# LeftInterface.net
KiCad netlist of a schematic drawn in Altium Designer
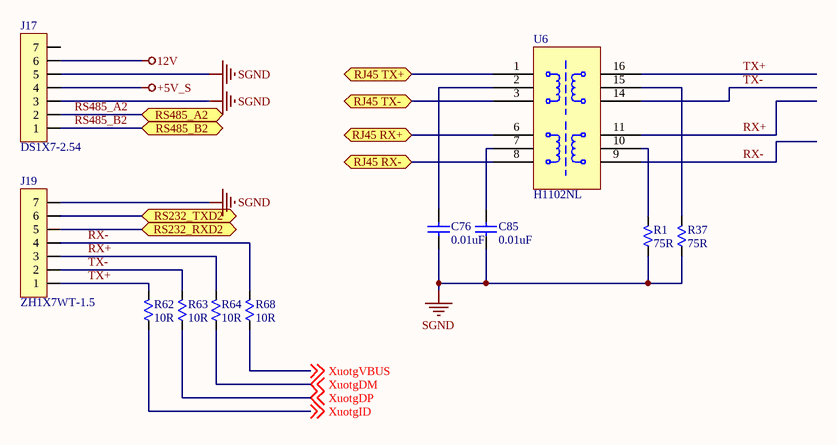
[diagram p0: LeftInterface.SchDoc]

(export (version "E")
  (design (tool "Eeschema 10.0.6"))
  (components
    (comp (ref "C76")
      (value "0.01uF")
      (footprint "C0805")
      (description "Capacitor")
      (fields (field (name "PUBLISHER") "Altium Limited"))
      (libsource (lib "Miscellaneous Devices") (part "Cap"))
    )
    (comp (ref "C85")
      (value "0.01uF")
      (footprint "C0805")
      (description "Capacitor")
      (fields (field (name "PUBLISHER") "Altium Limited"))
      (libsource (lib "Miscellaneous Devices") (part "Cap"))
    )
    (comp (ref "J17")
      (value "DS1X7-2.54")
      (footprint "DS1X7H-2.54")
      (libsource (lib "Connector Class") (part "HEADER1X7"))
    )
    (comp (ref "J19")
      (value "ZH1X7WT-1.5")
      (footprint "ZH1X7WT-1.5")
      (libsource (lib "Connector Class") (part "HEADER1X7"))
    )
    (comp (ref "R1")
      (value "75R")
      (footprint "R0805")
      (description "Resistor")
      (fields (field (name "PUBLISHER") "Altium Limited"))
      (libsource (lib "UP-Robot") (part "Res"))
    )
    (comp (ref "R37")
      (value "75R")
      (footprint "R0805")
      (description "Resistor")
      (fields (field (name "PUBLISHER") "Altium Limited"))
      (libsource (lib "UP-Robot") (part "Res"))
    )
    (comp (ref "R62")
      (value "10R")
      (footprint "R0805")
      (description "Resistor")
      (fields (field (name "PUBLISHER") "Altium Limited"))
      (libsource (lib "UP-Robot") (part "Res"))
    )
    (comp (ref "R63")
      (value "10R")
      (footprint "R0805")
      (description "Resistor")
      (fields (field (name "PUBLISHER") "Altium Limited"))
      (libsource (lib "UP-Robot") (part "Res"))
    )
    (comp (ref "R64")
      (value "10R")
      (footprint "R0805")
      (description "Resistor")
      (fields (field (name "PUBLISHER") "Altium Limited"))
      (libsource (lib "UP-Robot") (part "Res"))
    )
    (comp (ref "R68")
      (value "10R")
      (footprint "R0805")
      (description "Resistor")
      (fields (field (name "PUBLISHER") "Altium Limited"))
      (libsource (lib "UP-Robot") (part "Res"))
    )
    (comp (ref "U6")
      (value "H1102NL")
      (footprint "SOP16")
      (libsource (lib "Productor Class") (part "H1102NL"))
    )
  )
  (nets
    (net (code "1") (name "+5V_S") (class "Default")
      (node (ref "J17") (pin "4") (pinfunction "4_4") (pintype "passive"))
    )
    (net (code "2") (name "/RJ45 RX+") (class "Default") (node (ref "U6") (pin "6") (pintype "passive")))
    (net (code "3") (name "/RJ45 RX-") (class "Default") (node (ref "U6") (pin "8") (pintype "passive")))
    (net (code "4") (name "/RJ45 TX+") (class "Default") (node (ref "U6") (pin "1") (pintype "passive")))
    (net (code "5") (name "/RJ45 TX-") (class "Default") (node (ref "U6") (pin "3") (pintype "passive")))
    (net (code "6") (name "/RS232_RXD2") (class "Default")
      (node (ref "J19") (pin "5") (pinfunction "5_5") (pintype "passive"))
    )
    (net (code "7") (name "/RS232_TXD2") (class "Default")
      (node (ref "J19") (pin "6") (pinfunction "6_6") (pintype "passive"))
    )
    (net (code "8") (name "/RS485_A2") (class "Default")
      (node (ref "J17") (pin "2") (pinfunction "2_2") (pintype "passive"))
    )
    (net (code "9") (name "/RS485_B2") (class "Default")
      (node (ref "J17") (pin "1") (pinfunction "1_1") (pintype "passive"))
    )
    (net (code "10") (name "/RX+") (class "Default")
      (node (ref "J19") (pin "3") (pinfunction "3_3") (pintype "passive"))
      (node (ref "R64") (pin "1") (pinfunction "1_1") (pintype "passive"))
      (node (ref "U6") (pin "11") (pintype "passive"))
    )
    (net (code "11") (name "/RX-") (class "Default")
      (node (ref "J19") (pin "4") (pinfunction "4_4") (pintype "passive"))
      (node (ref "R68") (pin "1") (pinfunction "1_1") (pintype "passive"))
      (node (ref "U6") (pin "9") (pintype "passive"))
    )
    (net (code "12") (name "/TX+") (class "Default")
      (node (ref "J19") (pin "1") (pinfunction "1_1") (pintype "passive"))
      (node (ref "R62") (pin "1") (pinfunction "1_1") (pintype "passive"))
      (node (ref "U6") (pin "16") (pintype "passive"))
    )
    (net (code "13") (name "/TX-") (class "Default")
      (node (ref "J19") (pin "2") (pinfunction "2_2") (pintype "passive"))
      (node (ref "R63") (pin "1") (pinfunction "1_1") (pintype "passive"))
      (node (ref "U6") (pin "14") (pintype "passive"))
    )
    (net (code "14") (name "12V") (class "Default")
      (node (ref "J17") (pin "6") (pinfunction "6_6") (pintype "passive"))
    )
    (net (code "15") (name "Net-(C76-Pad1)") (class "Default")
      (node (ref "C76") (pin "1") (pinfunction "1_1") (pintype "passive"))
      (node (ref "U6") (pin "2") (pintype "passive"))
    )
    (net (code "16") (name "Net-(C85-Pad1)") (class "Default")
      (node (ref "C85") (pin "1") (pinfunction "1_1") (pintype "passive"))
      (node (ref "U6") (pin "7") (pintype "passive"))
    )
    (net (code "17") (name "Net-(R1-Pad1)") (class "Default")
      (node (ref "R1") (pin "1") (pinfunction "1_1") (pintype "passive"))
      (node (ref "U6") (pin "10") (pintype "passive"))
    )
    (net (code "18") (name "Net-(R37-Pad1)") (class "Default")
      (node (ref "R37") (pin "1") (pinfunction "1_1") (pintype "passive"))
      (node (ref "U6") (pin "15") (pintype "passive"))
    )
    (net (code "19") (name "SGND") (class "Default")
      (node (ref "C76") (pin "2") (pinfunction "2_2") (pintype "passive"))
      (node (ref "C85") (pin "2") (pinfunction "2_2") (pintype "passive"))
      (node (ref "J17") (pin "3") (pinfunction "3_3") (pintype "passive"))
      (node (ref "J17") (pin "5") (pinfunction "5_5") (pintype "passive"))
      (node (ref "J19") (pin "7") (pinfunction "7_7") (pintype "passive"))
      (node (ref "R1") (pin "2") (pinfunction "2_2") (pintype "passive"))
      (node (ref "R37") (pin "2") (pinfunction "2_2") (pintype "passive"))
    )
    (net (code "20") (name "XuotgDM") (class "Default")
      (node (ref "R64") (pin "2") (pinfunction "2_2") (pintype "passive"))
    )
    (net (code "21") (name "XuotgDP") (class "Default")
      (node (ref "R63") (pin "2") (pinfunction "2_2") (pintype "passive"))
    )
    (net (code "22") (name "XuotgID") (class "Default")
      (node (ref "R62") (pin "2") (pinfunction "2_2") (pintype "passive"))
    )
    (net (code "23") (name "XuotgVBUS") (class "Default")
      (node (ref "R68") (pin "2") (pinfunction "2_2") (pintype "passive"))
    )
    (net (code "24") (name "unconnected-(J17-Pad7)") (class "Default")
      (node (ref "J17") (pin "7") (pinfunction "7_7") (pintype "passive"))
    )
  )
)
